# IO_EXPAND.net
KiCad netlist of a schematic drawn in Altium Designer
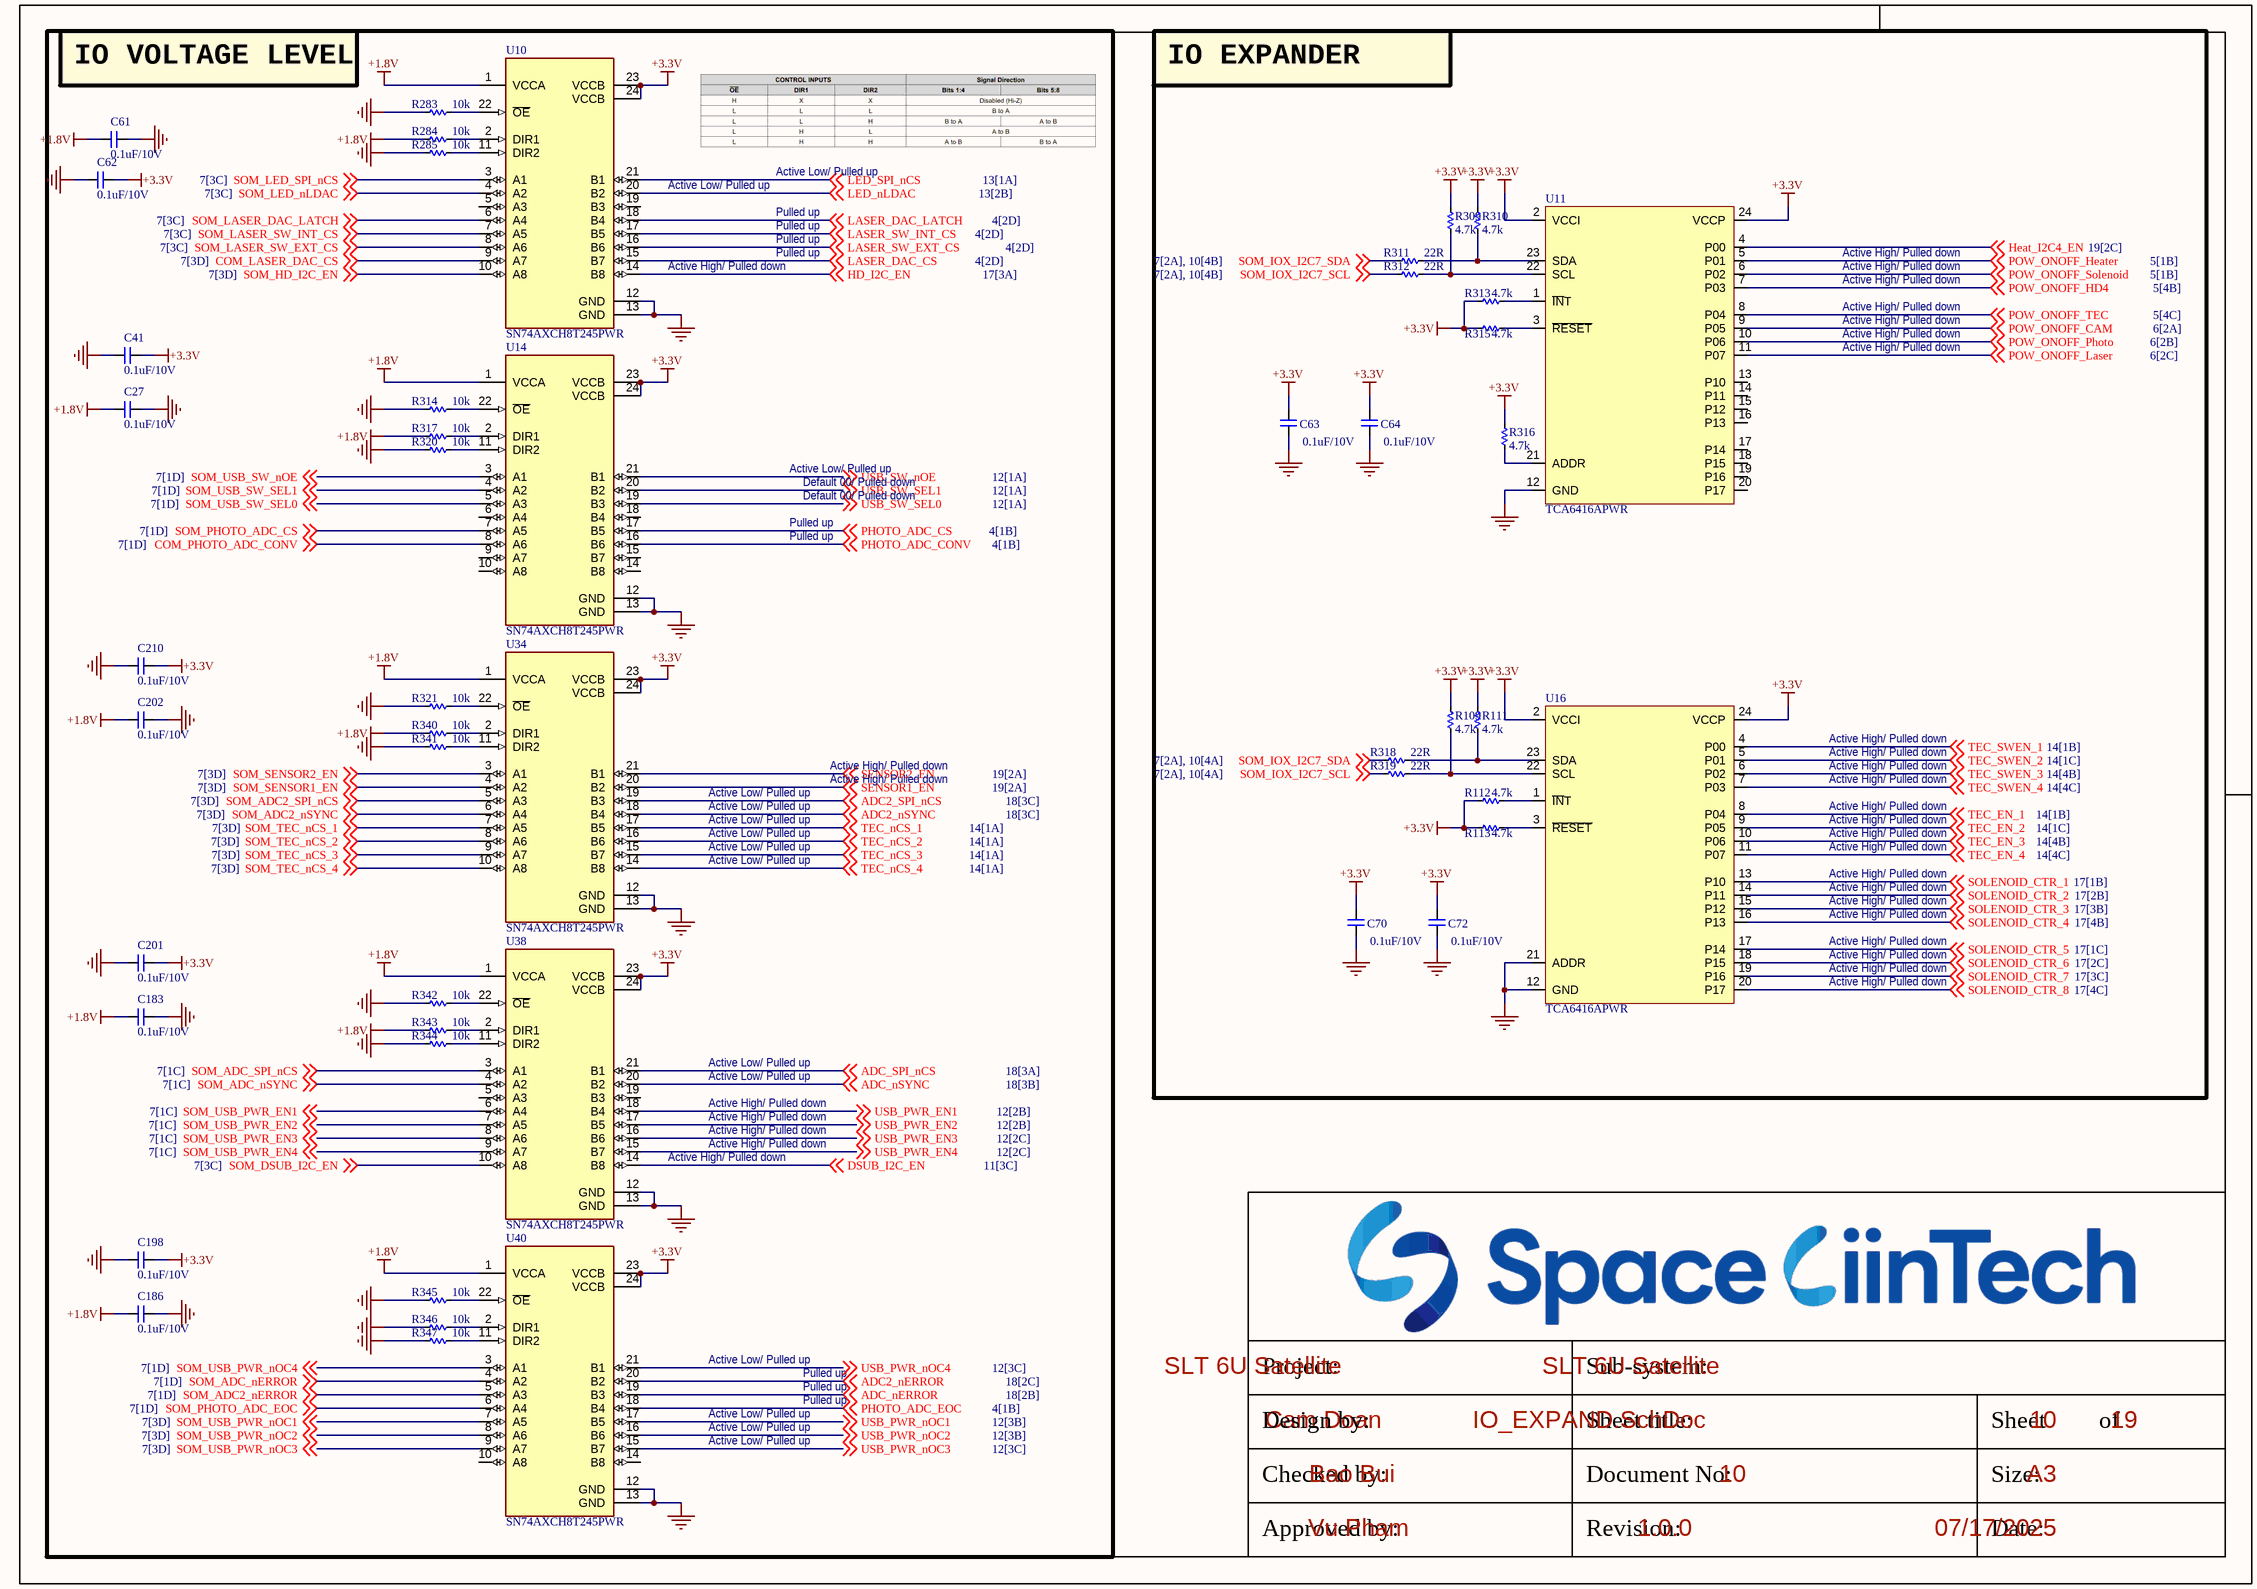
[diagram p0: IO_EXPAND.SchDoc]

(export (version "E")
  (design (tool "Eeschema 10.0.6"))
  (components
    (comp (ref "C27")
      (value "0.1uF/10V")
      (footprint "CAP_C_1005X60")
      (description "CAP CHIP")
      (libsource (lib "LABLIB") (part "_CAP_C_2"))
    )
    (comp (ref "C41")
      (value "0.1uF/10V")
      (footprint "CAP_C_1005X60")
      (description "CAP CHIP")
      (libsource (lib "LABLIB") (part "_CAP_C_2"))
    )
    (comp (ref "C61")
      (value "0.1uF/10V")
      (footprint "CAP_C_1005X60")
      (description "CAP CHIP")
      (libsource (lib "LABLIB") (part "_CAP_C_2"))
    )
    (comp (ref "C62")
      (value "0.1uF/10V")
      (footprint "CAP_C_1005X60")
      (description "CAP CHIP")
      (libsource (lib "LABLIB") (part "_CAP_C_2"))
    )
    (comp (ref "C63")
      (value "0.1uF/10V")
      (footprint "CAP_C_1005X60")
      (description "CAP CHIP")
      (libsource (lib "LABLIB") (part "_CAP_C_2"))
    )
    (comp (ref "C64")
      (value "0.1uF/10V")
      (footprint "CAP_C_1005X60")
      (description "CAP CHIP")
      (libsource (lib "LABLIB") (part "_CAP_C_2"))
    )
    (comp (ref "C70")
      (value "0.1uF/10V")
      (footprint "CAP_C_1005X60")
      (description "CAP CHIP")
      (libsource (lib "LABLIB") (part "_CAP_C_2"))
    )
    (comp (ref "C72")
      (value "0.1uF/10V")
      (footprint "CAP_C_1005X60")
      (description "CAP CHIP")
      (libsource (lib "LABLIB") (part "_CAP_C_2"))
    )
    (comp (ref "C183")
      (value "0.1uF/10V")
      (footprint "CAP_C_1005X60")
      (description "CAP CHIP")
      (libsource (lib "LABLIB") (part "_CAP_C_2"))
    )
    (comp (ref "C186")
      (value "0.1uF/10V")
      (footprint "CAP_C_1005X60")
      (description "CAP CHIP")
      (libsource (lib "LABLIB") (part "_CAP_C_2"))
    )
    (comp (ref "C198")
      (value "0.1uF/10V")
      (footprint "CAP_C_1005X60")
      (description "CAP CHIP")
      (libsource (lib "LABLIB") (part "_CAP_C_2"))
    )
    (comp (ref "C201")
      (value "0.1uF/10V")
      (footprint "CAP_C_1005X60")
      (description "CAP CHIP")
      (libsource (lib "LABLIB") (part "_CAP_C_2"))
    )
    (comp (ref "C202")
      (value "0.1uF/10V")
      (footprint "CAP_C_1005X60")
      (description "CAP CHIP")
      (libsource (lib "LABLIB") (part "_CAP_C_2"))
    )
    (comp (ref "C210")
      (value "0.1uF/10V")
      (footprint "CAP_C_1005X60")
      (description "CAP CHIP")
      (libsource (lib "LABLIB") (part "_CAP_C_2"))
    )
    (comp (ref "R109")
      (value "4.7k")
      (footprint "RES_C_1005X40")
      (description "RES")
      (libsource (lib "LABLIB") (part "_RES_B_2"))
    )
    (comp (ref "R111")
      (value "4.7k")
      (footprint "RES_C_1005X40")
      (description "RES")
      (libsource (lib "LABLIB") (part "_RES_B_2"))
    )
    (comp (ref "R112")
      (value "4.7k")
      (footprint "RES_C_1005X40")
      (description "RES")
      (libsource (lib "LABLIB") (part "_RES_B_2"))
    )
    (comp (ref "R113")
      (value "4.7k")
      (footprint "RES_C_1005X40")
      (description "RES")
      (libsource (lib "LABLIB") (part "_RES_B_2"))
    )
    (comp (ref "R283")
      (value "10k")
      (footprint "RES_C_1005X40")
      (description "RES")
      (libsource (lib "LABLIB") (part "_RES_B_2"))
    )
    (comp (ref "R284")
      (value "10k")
      (footprint "RES_C_1005X40")
      (description "RES")
      (libsource (lib "LABLIB") (part "_RES_B_2"))
    )
    (comp (ref "R285")
      (value "10k")
      (footprint "RES_C_1005X40")
      (description "RES")
      (libsource (lib "LABLIB") (part "_RES_B_2"))
    )
    (comp (ref "R309")
      (value "4.7k")
      (footprint "RES_C_1005X40")
      (description "RES")
      (libsource (lib "LABLIB") (part "_RES_B_2"))
    )
    (comp (ref "R310")
      (value "4.7k")
      (footprint "RES_C_1005X40")
      (description "RES")
      (libsource (lib "LABLIB") (part "_RES_B_2"))
    )
    (comp (ref "R311")
      (value "22R")
      (footprint "RES_C_1005X40")
      (description "RES")
      (libsource (lib "LABLIB") (part "_RES_B_2"))
    )
    (comp (ref "R312")
      (value "22R")
      (footprint "RES_C_1005X40")
      (description "RES")
      (libsource (lib "LABLIB") (part "_RES_B_2"))
    )
    (comp (ref "R313")
      (value "4.7k")
      (footprint "RES_C_1005X40")
      (description "RES")
      (libsource (lib "LABLIB") (part "_RES_B_2"))
    )
    (comp (ref "R314")
      (value "10k")
      (footprint "RES_C_1005X40")
      (description "RES")
      (libsource (lib "LABLIB") (part "_RES_B_2"))
    )
    (comp (ref "R315")
      (value "4.7k")
      (footprint "RES_C_1005X40")
      (description "RES")
      (libsource (lib "LABLIB") (part "_RES_B_2"))
    )
    (comp (ref "R316")
      (value "4.7k")
      (footprint "RES_C_1005X40")
      (description "RES")
      (libsource (lib "LABLIB") (part "_RES_B_2"))
    )
    (comp (ref "R317")
      (value "10k")
      (footprint "RES_C_1005X40")
      (description "RES")
      (libsource (lib "LABLIB") (part "_RES_B_2"))
    )
    (comp (ref "R318")
      (value "22R")
      (footprint "RES_C_1005X40")
      (description "RES")
      (libsource (lib "LABLIB") (part "_RES_B_2"))
    )
    (comp (ref "R319")
      (value "22R")
      (footprint "RES_C_1005X40")
      (description "RES")
      (libsource (lib "LABLIB") (part "_RES_B_2"))
    )
    (comp (ref "R320")
      (value "10k")
      (footprint "RES_C_1005X40")
      (description "RES")
      (libsource (lib "LABLIB") (part "_RES_B_2"))
    )
    (comp (ref "R321")
      (value "10k")
      (footprint "RES_C_1005X40")
      (description "RES")
      (libsource (lib "LABLIB") (part "_RES_B_2"))
    )
    (comp (ref "R340")
      (value "10k")
      (footprint "RES_C_1005X40")
      (description "RES")
      (libsource (lib "LABLIB") (part "_RES_B_2"))
    )
    (comp (ref "R341")
      (value "10k")
      (footprint "RES_C_1005X40")
      (description "RES")
      (libsource (lib "LABLIB") (part "_RES_B_2"))
    )
    (comp (ref "R342")
      (value "10k")
      (footprint "RES_C_1005X40")
      (description "RES")
      (libsource (lib "LABLIB") (part "_RES_B_2"))
    )
    (comp (ref "R343")
      (value "10k")
      (footprint "RES_C_1005X40")
      (description "RES")
      (libsource (lib "LABLIB") (part "_RES_B_2"))
    )
    (comp (ref "R344")
      (value "10k")
      (footprint "RES_C_1005X40")
      (description "RES")
      (libsource (lib "LABLIB") (part "_RES_B_2"))
    )
    (comp (ref "R345")
      (value "10k")
      (footprint "RES_C_1005X40")
      (description "RES")
      (libsource (lib "LABLIB") (part "_RES_B_2"))
    )
    (comp (ref "R346")
      (value "10k")
      (footprint "RES_C_1005X40")
      (description "RES")
      (libsource (lib "LABLIB") (part "_RES_B_2"))
    )
    (comp (ref "R347")
      (value "10k")
      (footprint "RES_C_1005X40")
      (description "RES")
      (libsource (lib "LABLIB") (part "_RES_B_2"))
    )
    (comp (ref "U10")
      (value "SN74AXCH8T245PWR")
      (footprint "SOP65P640X120-24N")
      (description "8-Bit Dual-Supply Bus Transceiver")
      (fields (field (name "MF") "Texas Instruments"))
      (libsource (lib "LABLIB") (part "IC_voltage_level_SN74AXCH8T245PWR"))
    )
    (comp (ref "U11")
      (value "TCA6416APWR")
      (footprint "SOP65P440W-24N")
      (libsource (lib "CAMERA_SchLib") (part "IC_I2Cto16IO_TCA6416APWR"))
    )
    (comp (ref "U14")
      (value "SN74AXCH8T245PWR")
      (footprint "SOP65P640X120-24N")
      (description "8-Bit Dual-Supply Bus Transceiver")
      (fields (field (name "MF") "Texas Instruments"))
      (libsource (lib "LABLIB") (part "IC_voltage_level_SN74AXCH8T245PWR"))
    )
    (comp (ref "U16")
      (value "TCA6416APWR")
      (footprint "SOP65P440W-24N")
      (libsource (lib "CAMERA_SchLib") (part "IC_I2Cto16IO_TCA6416APWR"))
    )
    (comp (ref "U34")
      (value "SN74AXCH8T245PWR")
      (footprint "SOP65P640X120-24N")
      (description "8-Bit Dual-Supply Bus Transceiver")
      (fields (field (name "MF") "Texas Instruments"))
      (libsource (lib "LABLIB") (part "IC_voltage_level_SN74AXCH8T245PWR"))
    )
    (comp (ref "U38")
      (value "SN74AXCH8T245PWR")
      (footprint "SOP65P640X120-24N")
      (description "8-Bit Dual-Supply Bus Transceiver")
      (fields (field (name "MF") "Texas Instruments"))
      (libsource (lib "LABLIB") (part "IC_voltage_level_SN74AXCH8T245PWR"))
    )
    (comp (ref "U40")
      (value "SN74AXCH8T245PWR")
      (footprint "SOP65P640X120-24N")
      (description "8-Bit Dual-Supply Bus Transceiver")
      (fields (field (name "MF") "Texas Instruments"))
      (libsource (lib "LABLIB") (part "IC_voltage_level_SN74AXCH8T245PWR"))
    )
  )
  (nets
    (net (code "1") (name "+1.8V") (class "Default")
      (node (ref "C183") (pin "2") (pinfunction "2_2") (pintype "passive"))
      (node (ref "C186") (pin "2") (pinfunction "2_2") (pintype "passive"))
      (node (ref "C202") (pin "2") (pinfunction "2_2") (pintype "passive"))
      (node (ref "C27") (pin "2") (pinfunction "2_2") (pintype "passive"))
      (node (ref "C61") (pin "2") (pinfunction "2_2") (pintype "passive"))
      (node (ref "R284") (pin "2") (pinfunction "2_2") (pintype "passive"))
      (node (ref "R317") (pin "2") (pinfunction "2_2") (pintype "passive"))
      (node (ref "R340") (pin "2") (pinfunction "2_2") (pintype "passive"))
      (node (ref "R343") (pin "2") (pinfunction "2_2") (pintype "passive"))
      (node (ref "U10") (pin "1") (pinfunction "VCCA_1") (pintype "power_in"))
      (node (ref "U14") (pin "1") (pinfunction "VCCA_1") (pintype "power_in"))
      (node (ref "U34") (pin "1") (pinfunction "VCCA_1") (pintype "power_in"))
      (node (ref "U38") (pin "1") (pinfunction "VCCA_1") (pintype "power_in"))
      (node (ref "U40") (pin "1") (pinfunction "VCCA_1") (pintype "power_in"))
    )
    (net (code "2") (name "+3.3V") (class "Default")
      (node (ref "C198") (pin "2") (pinfunction "2_2") (pintype "passive"))
      (node (ref "C201") (pin "2") (pinfunction "2_2") (pintype "passive"))
      (node (ref "C210") (pin "2") (pinfunction "2_2") (pintype "passive"))
      (node (ref "C41") (pin "2") (pinfunction "2_2") (pintype "passive"))
      (node (ref "C62") (pin "2") (pinfunction "2_2") (pintype "passive"))
      (node (ref "C63") (pin "2") (pinfunction "2_2") (pintype "passive"))
      (node (ref "C64") (pin "2") (pinfunction "2_2") (pintype "passive"))
      (node (ref "C70") (pin "2") (pinfunction "2_2") (pintype "passive"))
      (node (ref "C72") (pin "2") (pinfunction "2_2") (pintype "passive"))
      (node (ref "R109") (pin "1") (pinfunction "1_1") (pintype "passive"))
      (node (ref "R111") (pin "1") (pinfunction "1_1") (pintype "passive"))
      (node (ref "R112") (pin "1") (pinfunction "1_1") (pintype "passive"))
      (node (ref "R113") (pin "1") (pinfunction "1_1") (pintype "passive"))
      (node (ref "R309") (pin "1") (pinfunction "1_1") (pintype "passive"))
      (node (ref "R310") (pin "1") (pinfunction "1_1") (pintype "passive"))
      (node (ref "R313") (pin "1") (pinfunction "1_1") (pintype "passive"))
      (node (ref "R315") (pin "1") (pinfunction "1_1") (pintype "passive"))
      (node (ref "R316") (pin "2") (pinfunction "2_2") (pintype "passive"))
      (node (ref "U10") (pin "23") (pinfunction "VCCB_23") (pintype "power_in"))
      (node (ref "U10") (pin "24") (pinfunction "VCCB_24") (pintype "power_in"))
      (node (ref "U11") (pin "2") (pinfunction "VCCI_2") (pintype "passive"))
      (node (ref "U11") (pin "24") (pinfunction "VCCP_24") (pintype "passive"))
      (node (ref "U14") (pin "23") (pinfunction "VCCB_23") (pintype "power_in"))
      (node (ref "U14") (pin "24") (pinfunction "VCCB_24") (pintype "power_in"))
      (node (ref "U16") (pin "2") (pinfunction "VCCI_2") (pintype "passive"))
      (node (ref "U16") (pin "24") (pinfunction "VCCP_24") (pintype "passive"))
      (node (ref "U34") (pin "23") (pinfunction "VCCB_23") (pintype "power_in"))
      (node (ref "U34") (pin "24") (pinfunction "VCCB_24") (pintype "power_in"))
      (node (ref "U38") (pin "23") (pinfunction "VCCB_23") (pintype "power_in"))
      (node (ref "U38") (pin "24") (pinfunction "VCCB_24") (pintype "power_in"))
      (node (ref "U40") (pin "23") (pinfunction "VCCB_23") (pintype "power_in"))
      (node (ref "U40") (pin "24") (pinfunction "VCCB_24") (pintype "power_in"))
    )
    (net (code "3") (name "ADC2_SPI_nCS") (class "Default")
      (node (ref "U34") (pin "19") (pinfunction "B3_19") (pintype "bidirectional"))
    )
    (net (code "4") (name "ADC2_nERROR") (class "Default")
      (node (ref "U40") (pin "20") (pinfunction "B2_20") (pintype "bidirectional"))
    )
    (net (code "5") (name "ADC2_nSYNC") (class "Default")
      (node (ref "U34") (pin "18") (pinfunction "B4_18") (pintype "bidirectional"))
    )
    (net (code "6") (name "ADC_SPI_nCS") (class "Default")
      (node (ref "U38") (pin "21") (pinfunction "B1_21") (pintype "bidirectional"))
    )
    (net (code "7") (name "ADC_nERROR") (class "Default")
      (node (ref "U40") (pin "19") (pinfunction "B3_19") (pintype "bidirectional"))
    )
    (net (code "8") (name "ADC_nSYNC") (class "Default")
      (node (ref "U38") (pin "20") (pinfunction "B2_20") (pintype "bidirectional"))
    )
    (net (code "9") (name "COM_LASER_DAC_CS") (class "Default")
      (node (ref "U10") (pin "9") (pinfunction "A7_9") (pintype "bidirectional"))
    )
    (net (code "10") (name "COM_PHOTO_ADC_CONV") (class "Default")
      (node (ref "U14") (pin "8") (pinfunction "A6_8") (pintype "bidirectional"))
    )
    (net (code "11") (name "DSUB_I2C_EN") (class "Default")
      (node (ref "U38") (pin "14") (pinfunction "B8_14") (pintype "bidirectional"))
    )
    (net (code "12") (name "GND") (class "Default")
      (node (ref "C183") (pin "1") (pinfunction "1_1") (pintype "passive"))
      (node (ref "C186") (pin "1") (pinfunction "1_1") (pintype "passive"))
      (node (ref "C198") (pin "1") (pinfunction "1_1") (pintype "passive"))
      (node (ref "C201") (pin "1") (pinfunction "1_1") (pintype "passive"))
      (node (ref "C202") (pin "1") (pinfunction "1_1") (pintype "passive"))
      (node (ref "C210") (pin "1") (pinfunction "1_1") (pintype "passive"))
      (node (ref "C27") (pin "1") (pinfunction "1_1") (pintype "passive"))
      (node (ref "C41") (pin "1") (pinfunction "1_1") (pintype "passive"))
      (node (ref "C61") (pin "1") (pinfunction "1_1") (pintype "passive"))
      (node (ref "C62") (pin "1") (pinfunction "1_1") (pintype "passive"))
      (node (ref "C63") (pin "1") (pinfunction "1_1") (pintype "passive"))
      (node (ref "C64") (pin "1") (pinfunction "1_1") (pintype "passive"))
      (node (ref "C70") (pin "1") (pinfunction "1_1") (pintype "passive"))
      (node (ref "C72") (pin "1") (pinfunction "1_1") (pintype "passive"))
      (node (ref "R283") (pin "2") (pinfunction "2_2") (pintype "passive"))
      (node (ref "R285") (pin "2") (pinfunction "2_2") (pintype "passive"))
      (node (ref "R314") (pin "2") (pinfunction "2_2") (pintype "passive"))
      (node (ref "R320") (pin "2") (pinfunction "2_2") (pintype "passive"))
      (node (ref "R321") (pin "2") (pinfunction "2_2") (pintype "passive"))
      (node (ref "R341") (pin "2") (pinfunction "2_2") (pintype "passive"))
      (node (ref "R342") (pin "2") (pinfunction "2_2") (pintype "passive"))
      (node (ref "R344") (pin "2") (pinfunction "2_2") (pintype "passive"))
      (node (ref "R345") (pin "2") (pinfunction "2_2") (pintype "passive"))
      (node (ref "R346") (pin "2") (pinfunction "2_2") (pintype "passive"))
      (node (ref "R347") (pin "2") (pinfunction "2_2") (pintype "passive"))
      (node (ref "U10") (pin "12") (pinfunction "GND_12") (pintype "power_in"))
      (node (ref "U10") (pin "13") (pinfunction "GND_13") (pintype "power_in"))
      (node (ref "U11") (pin "12") (pinfunction "GND_12") (pintype "passive"))
      (node (ref "U14") (pin "12") (pinfunction "GND_12") (pintype "power_in"))
      (node (ref "U14") (pin "13") (pinfunction "GND_13") (pintype "power_in"))
      (node (ref "U16") (pin "12") (pinfunction "GND_12") (pintype "passive"))
      (node (ref "U16") (pin "21") (pinfunction "ADDR_21") (pintype "passive"))
      (node (ref "U34") (pin "12") (pinfunction "GND_12") (pintype "power_in"))
      (node (ref "U34") (pin "13") (pinfunction "GND_13") (pintype "power_in"))
      (node (ref "U38") (pin "12") (pinfunction "GND_12") (pintype "power_in"))
      (node (ref "U38") (pin "13") (pinfunction "GND_13") (pintype "power_in"))
      (node (ref "U40") (pin "12") (pinfunction "GND_12") (pintype "power_in"))
      (node (ref "U40") (pin "13") (pinfunction "GND_13") (pintype "power_in"))
    )
    (net (code "13") (name "HD_I2C_EN") (class "Default")
      (node (ref "U10") (pin "14") (pinfunction "B8_14") (pintype "bidirectional"))
    )
    (net (code "14") (name "Heat_I2C4_EN") (class "Default")
      (node (ref "U11") (pin "4") (pinfunction "P00_4") (pintype "passive"))
    )
    (net (code "15") (name "LASER_DAC_CS") (class "Default")
      (node (ref "U10") (pin "15") (pinfunction "B7_15") (pintype "bidirectional"))
    )
    (net (code "16") (name "LASER_DAC_LATCH") (class "Default")
      (node (ref "U10") (pin "18") (pinfunction "B4_18") (pintype "bidirectional"))
    )
    (net (code "17") (name "LASER_SW_EXT_CS") (class "Default")
      (node (ref "U10") (pin "16") (pinfunction "B6_16") (pintype "bidirectional"))
    )
    (net (code "18") (name "LASER_SW_INT_CS") (class "Default")
      (node (ref "U10") (pin "17") (pinfunction "B5_17") (pintype "bidirectional"))
    )
    (net (code "19") (name "LED_SPI_nCS") (class "Default")
      (node (ref "U10") (pin "21") (pinfunction "B1_21") (pintype "bidirectional"))
    )
    (net (code "20") (name "LED_nLDAC") (class "Default")
      (node (ref "U10") (pin "20") (pinfunction "B2_20") (pintype "bidirectional"))
    )
    (net (code "21") (name "Net-(U10-DIR1)") (class "Default")
      (node (ref "R284") (pin "1") (pinfunction "1_1") (pintype "passive"))
      (node (ref "U10") (pin "2") (pinfunction "DIR1_2") (pintype "input"))
    )
    (net (code "22") (name "Net-(U10-DIR2)") (class "Default")
      (node (ref "R285") (pin "1") (pinfunction "1_1") (pintype "passive"))
      (node (ref "U10") (pin "11") (pinfunction "DIR2_11") (pintype "input"))
    )
    (net (code "23") (name "Net-(U10-~{OE})") (class "Default")
      (node (ref "R283") (pin "1") (pinfunction "1_1") (pintype "passive"))
      (node (ref "U10") (pin "22") (pinfunction "~{OE}_22") (pintype "input"))
    )
    (net (code "24") (name "Net-(U11-ADDR)") (class "Default")
      (node (ref "R316") (pin "1") (pinfunction "1_1") (pintype "passive"))
      (node (ref "U11") (pin "21") (pinfunction "ADDR_21") (pintype "passive"))
    )
    (net (code "25") (name "Net-(U11-SCL)") (class "Default")
      (node (ref "R309") (pin "2") (pinfunction "2_2") (pintype "passive"))
      (node (ref "R312") (pin "2") (pinfunction "2_2") (pintype "passive"))
      (node (ref "U11") (pin "22") (pinfunction "SCL_22") (pintype "passive"))
    )
    (net (code "26") (name "Net-(U11-SDA)") (class "Default")
      (node (ref "R310") (pin "2") (pinfunction "2_2") (pintype "passive"))
      (node (ref "R311") (pin "2") (pinfunction "2_2") (pintype "passive"))
      (node (ref "U11") (pin "23") (pinfunction "SDA_23") (pintype "passive"))
    )
    (net (code "27") (name "Net-(U11-~{IN}T)") (class "Default")
      (node (ref "R313") (pin "2") (pinfunction "2_2") (pintype "passive"))
      (node (ref "U11") (pin "1") (pinfunction "~{IN}T_1") (pintype "passive"))
    )
    (net (code "28") (name "Net-(U11-~{RESET})") (class "Default")
      (node (ref "R315") (pin "2") (pinfunction "2_2") (pintype "passive"))
      (node (ref "U11") (pin "3") (pinfunction "~{RESET}_3") (pintype "passive"))
    )
    (net (code "29") (name "Net-(U14-DIR1)") (class "Default")
      (node (ref "R317") (pin "1") (pinfunction "1_1") (pintype "passive"))
      (node (ref "U14") (pin "2") (pinfunction "DIR1_2") (pintype "input"))
    )
    (net (code "30") (name "Net-(U14-DIR2)") (class "Default")
      (node (ref "R320") (pin "1") (pinfunction "1_1") (pintype "passive"))
      (node (ref "U14") (pin "11") (pinfunction "DIR2_11") (pintype "input"))
    )
    (net (code "31") (name "Net-(U14-~{OE})") (class "Default")
      (node (ref "R314") (pin "1") (pinfunction "1_1") (pintype "passive"))
      (node (ref "U14") (pin "22") (pinfunction "~{OE}_22") (pintype "input"))
    )
    (net (code "32") (name "Net-(U16-SCL)") (class "Default")
      (node (ref "R109") (pin "2") (pinfunction "2_2") (pintype "passive"))
      (node (ref "R319") (pin "2") (pinfunction "2_2") (pintype "passive"))
      (node (ref "U16") (pin "22") (pinfunction "SCL_22") (pintype "passive"))
    )
    (net (code "33") (name "Net-(U16-SDA)") (class "Default")
      (node (ref "R111") (pin "2") (pinfunction "2_2") (pintype "passive"))
      (node (ref "R318") (pin "2") (pinfunction "2_2") (pintype "passive"))
      (node (ref "U16") (pin "23") (pinfunction "SDA_23") (pintype "passive"))
    )
    (net (code "34") (name "Net-(U16-~{IN}T)") (class "Default")
      (node (ref "R112") (pin "2") (pinfunction "2_2") (pintype "passive"))
      (node (ref "U16") (pin "1") (pinfunction "~{IN}T_1") (pintype "passive"))
    )
    (net (code "35") (name "Net-(U16-~{RESET})") (class "Default")
      (node (ref "R113") (pin "2") (pinfunction "2_2") (pintype "passive"))
      (node (ref "U16") (pin "3") (pinfunction "~{RESET}_3") (pintype "passive"))
    )
    (net (code "36") (name "Net-(U34-DIR1)") (class "Default")
      (node (ref "R340") (pin "1") (pinfunction "1_1") (pintype "passive"))
      (node (ref "U34") (pin "2") (pinfunction "DIR1_2") (pintype "input"))
    )
    (net (code "37") (name "Net-(U34-DIR2)") (class "Default")
      (node (ref "R341") (pin "1") (pinfunction "1_1") (pintype "passive"))
      (node (ref "U34") (pin "11") (pinfunction "DIR2_11") (pintype "input"))
    )
    (net (code "38") (name "Net-(U34-~{OE})") (class "Default")
      (node (ref "R321") (pin "1") (pinfunction "1_1") (pintype "passive"))
      (node (ref "U34") (pin "22") (pinfunction "~{OE}_22") (pintype "input"))
    )
    (net (code "39") (name "Net-(U38-DIR1)") (class "Default")
      (node (ref "R343") (pin "1") (pinfunction "1_1") (pintype "passive"))
      (node (ref "U38") (pin "2") (pinfunction "DIR1_2") (pintype "input"))
    )
    (net (code "40") (name "Net-(U38-DIR2)") (class "Default")
      (node (ref "R344") (pin "1") (pinfunction "1_1") (pintype "passive"))
      (node (ref "U38") (pin "11") (pinfunction "DIR2_11") (pintype "input"))
    )
    (net (code "41") (name "Net-(U38-~{OE})") (class "Default")
      (node (ref "R342") (pin "1") (pinfunction "1_1") (pintype "passive"))
      (node (ref "U38") (pin "22") (pinfunction "~{OE}_22") (pintype "input"))
    )
    (net (code "42") (name "Net-(U40-DIR1)") (class "Default")
      (node (ref "R346") (pin "1") (pinfunction "1_1") (pintype "passive"))
      (node (ref "U40") (pin "2") (pinfunction "DIR1_2") (pintype "input"))
    )
    (net (code "43") (name "Net-(U40-DIR2)") (class "Default")
      (node (ref "R347") (pin "1") (pinfunction "1_1") (pintype "passive"))
      (node (ref "U40") (pin "11") (pinfunction "DIR2_11") (pintype "input"))
    )
    (net (code "44") (name "Net-(U40-~{OE})") (class "Default")
      (node (ref "R345") (pin "1") (pinfunction "1_1") (pintype "passive"))
      (node (ref "U40") (pin "22") (pinfunction "~{OE}_22") (pintype "input"))
    )
    (net (code "45") (name "PHOTO_ADC_CONV") (class "Default")
      (node (ref "U14") (pin "16") (pinfunction "B6_16") (pintype "bidirectional"))
    )
    (net (code "46") (name "PHOTO_ADC_CS") (class "Default")
      (node (ref "U14") (pin "17") (pinfunction "B5_17") (pintype "bidirectional"))
    )
    (net (code "47") (name "PHOTO_ADC_EOC") (class "Default")
      (node (ref "U40") (pin "18") (pinfunction "B4_18") (pintype "bidirectional"))
    )
    (net (code "48") (name "POW_ONOFF_CAM") (class "Default")
      (node (ref "U11") (pin "9") (pinfunction "P05_9") (pintype "passive"))
    )
    (net (code "49") (name "POW_ONOFF_HD4") (class "Default")
      (node (ref "U11") (pin "7") (pinfunction "P03_7") (pintype "passive"))
    )
    (net (code "50") (name "POW_ONOFF_Heater") (class "Default")
      (node (ref "U11") (pin "5") (pinfunction "P01_5") (pintype "passive"))
    )
    (net (code "51") (name "POW_ONOFF_Laser") (class "Default")
      (node (ref "U11") (pin "11") (pinfunction "P07_11") (pintype "passive"))
    )
    (net (code "52") (name "POW_ONOFF_Photo") (class "Default")
      (node (ref "U11") (pin "10") (pinfunction "P06_10") (pintype "passive"))
    )
    (net (code "53") (name "POW_ONOFF_Solenoid") (class "Default")
      (node (ref "U11") (pin "6") (pinfunction "P02_6") (pintype "passive"))
    )
    (net (code "54") (name "POW_ONOFF_TEC") (class "Default")
      (node (ref "U11") (pin "8") (pinfunction "P04_8") (pintype "passive"))
    )
    (net (code "55") (name "SENSOR1_EN") (class "Default")
      (node (ref "U34") (pin "20") (pinfunction "B2_20") (pintype "bidirectional"))
    )
    (net (code "56") (name "SENSOR2_EN") (class "Default")
      (node (ref "U34") (pin "21") (pinfunction "B1_21") (pintype "bidirectional"))
    )
    (net (code "57") (name "SOLENOID_CTR_1") (class "Default")
      (node (ref "U16") (pin "13") (pinfunction "P10_13") (pintype "passive"))
    )
    (net (code "58") (name "SOLENOID_CTR_2") (class "Default")
      (node (ref "U16") (pin "14") (pinfunction "P11_14") (pintype "passive"))
    )
    (net (code "59") (name "SOLENOID_CTR_3") (class "Default")
      (node (ref "U16") (pin "15") (pinfunction "P12_15") (pintype "passive"))
    )
    (net (code "60") (name "SOLENOID_CTR_4") (class "Default")
      (node (ref "U16") (pin "16") (pinfunction "P13_16") (pintype "passive"))
    )
    (net (code "61") (name "SOLENOID_CTR_5") (class "Default")
      (node (ref "U16") (pin "17") (pinfunction "P14_17") (pintype "passive"))
    )
    (net (code "62") (name "SOLENOID_CTR_6") (class "Default")
      (node (ref "U16") (pin "18") (pinfunction "P15_18") (pintype "passive"))
    )
    (net (code "63") (name "SOLENOID_CTR_7") (class "Default")
      (node (ref "U16") (pin "19") (pinfunction "P16_19") (pintype "passive"))
    )
    (net (code "64") (name "SOLENOID_CTR_8") (class "Default")
      (node (ref "U16") (pin "20") (pinfunction "P17_20") (pintype "passive"))
    )
    (net (code "65") (name "SOM_ADC2_SPI_nCS") (class "Default")
      (node (ref "U34") (pin "5") (pinfunction "A3_5") (pintype "bidirectional"))
    )
    (net (code "66") (name "SOM_ADC2_nERROR") (class "Default")
      (node (ref "U40") (pin "5") (pinfunction "A3_5") (pintype "bidirectional"))
    )
    (net (code "67") (name "SOM_ADC2_nSYNC") (class "Default")
      (node (ref "U34") (pin "6") (pinfunction "A4_6") (pintype "bidirectional"))
    )
    (net (code "68") (name "SOM_ADC_SPI_nCS") (class "Default")
      (node (ref "U38") (pin "3") (pinfunction "A1_3") (pintype "bidirectional"))
    )
    (net (code "69") (name "SOM_ADC_nERROR") (class "Default")
      (node (ref "U40") (pin "4") (pinfunction "A2_4") (pintype "bidirectional"))
    )
    (net (code "70") (name "SOM_ADC_nSYNC") (class "Default")
      (node (ref "U38") (pin "4") (pinfunction "A2_4") (pintype "bidirectional"))
    )
    (net (code "71") (name "SOM_DSUB_I2C_EN") (class "Default")
      (node (ref "U38") (pin "10") (pinfunction "A8_10") (pintype "bidirectional"))
    )
    (net (code "72") (name "SOM_HD_I2C_EN") (class "Default")
      (node (ref "U10") (pin "10") (pinfunction "A8_10") (pintype "bidirectional"))
    )
    (net (code "73") (name "SOM_IOX_I2C7_SCL") (class "Default")
      (node (ref "R312") (pin "1") (pinfunction "1_1") (pintype "passive"))
      (node (ref "R319") (pin "1") (pinfunction "1_1") (pintype "passive"))
    )
    (net (code "74") (name "SOM_IOX_I2C7_SDA") (class "Default")
      (node (ref "R311") (pin "1") (pinfunction "1_1") (pintype "passive"))
      (node (ref "R318") (pin "1") (pinfunction "1_1") (pintype "passive"))
    )
    (net (code "75") (name "SOM_LASER_DAC_LATCH") (class "Default")
      (node (ref "U10") (pin "6") (pinfunction "A4_6") (pintype "bidirectional"))
    )
    (net (code "76") (name "SOM_LASER_SW_EXT_CS") (class "Default")
      (node (ref "U10") (pin "8") (pinfunction "A6_8") (pintype "bidirectional"))
    )
    (net (code "77") (name "SOM_LASER_SW_INT_CS") (class "Default")
      (node (ref "U10") (pin "7") (pinfunction "A5_7") (pintype "bidirectional"))
    )
    (net (code "78") (name "SOM_LED_SPI_nCS") (class "Default")
      (node (ref "U10") (pin "3") (pinfunction "A1_3") (pintype "bidirectional"))
    )
    (net (code "79") (name "SOM_LED_nLDAC") (class "Default")
      (node (ref "U10") (pin "4") (pinfunction "A2_4") (pintype "bidirectional"))
    )
    (net (code "80") (name "SOM_PHOTO_ADC_CS") (class "Default")
      (node (ref "U14") (pin "7") (pinfunction "A5_7") (pintype "bidirectional"))
    )
    (net (code "81") (name "SOM_PHOTO_ADC_EOC") (class "Default")
      (node (ref "U40") (pin "6") (pinfunction "A4_6") (pintype "bidirectional"))
    )
    (net (code "82") (name "SOM_SENSOR1_EN") (class "Default")
      (node (ref "U34") (pin "4") (pinfunction "A2_4") (pintype "bidirectional"))
    )
    (net (code "83") (name "SOM_SENSOR2_EN") (class "Default")
      (node (ref "U34") (pin "3") (pinfunction "A1_3") (pintype "bidirectional"))
    )
    (net (code "84") (name "SOM_TEC_nCS_1") (class "Default")
      (node (ref "U34") (pin "7") (pinfunction "A5_7") (pintype "bidirectional"))
    )
    (net (code "85") (name "SOM_TEC_nCS_2") (class "Default")
      (node (ref "U34") (pin "8") (pinfunction "A6_8") (pintype "bidirectional"))
    )
    (net (code "86") (name "SOM_TEC_nCS_3") (class "Default")
      (node (ref "U34") (pin "9") (pinfunction "A7_9") (pintype "bidirectional"))
    )
    (net (code "87") (name "SOM_TEC_nCS_4") (class "Default")
      (node (ref "U34") (pin "10") (pinfunction "A8_10") (pintype "bidirectional"))
    )
    (net (code "88") (name "SOM_USB_PWR_EN1") (class "Default")
      (node (ref "U38") (pin "6") (pinfunction "A4_6") (pintype "bidirectional"))
    )
    (net (code "89") (name "SOM_USB_PWR_EN2") (class "Default")
      (node (ref "U38") (pin "7") (pinfunction "A5_7") (pintype "bidirectional"))
    )
    (net (code "90") (name "SOM_USB_PWR_EN3") (class "Default")
      (node (ref "U38") (pin "8") (pinfunction "A6_8") (pintype "bidirectional"))
    )
    (net (code "91") (name "SOM_USB_PWR_EN4") (class "Default")
      (node (ref "U38") (pin "9") (pinfunction "A7_9") (pintype "bidirectional"))
    )
    (net (code "92") (name "SOM_USB_PWR_nOC1") (class "Default")
      (node (ref "U40") (pin "7") (pinfunction "A5_7") (pintype "bidirectional"))
    )
    (net (code "93") (name "SOM_USB_PWR_nOC2") (class "Default")
      (node (ref "U40") (pin "8") (pinfunction "A6_8") (pintype "bidirectional"))
    )
    (net (code "94") (name "SOM_USB_PWR_nOC3") (class "Default")
      (node (ref "U40") (pin "9") (pinfunction "A7_9") (pintype "bidirectional"))
    )
    (net (code "95") (name "SOM_USB_PWR_nOC4") (class "Default")
      (node (ref "U40") (pin "3") (pinfunction "A1_3") (pintype "bidirectional"))
    )
    (net (code "96") (name "SOM_USB_SW_SEL0") (class "Default")
      (node (ref "U14") (pin "5") (pinfunction "A3_5") (pintype "bidirectional"))
    )
    (net (code "97") (name "SOM_USB_SW_SEL1") (class "Default")
      (node (ref "U14") (pin "4") (pinfunction "A2_4") (pintype "bidirectional"))
    )
    (net (code "98") (name "SOM_USB_SW_nOE") (class "Default")
      (node (ref "U14") (pin "3") (pinfunction "A1_3") (pintype "bidirectional"))
    )
    (net (code "99") (name "TEC_EN_1") (class "Default")
      (node (ref "U16") (pin "8") (pinfunction "P04_8") (pintype "passive"))
    )
    (net (code "100") (name "TEC_EN_2") (class "Default")
      (node (ref "U16") (pin "9") (pinfunction "P05_9") (pintype "passive"))
    )
    (net (code "101") (name "TEC_EN_3") (class "Default")
      (node (ref "U16") (pin "10") (pinfunction "P06_10") (pintype "passive"))
    )
    (net (code "102") (name "TEC_EN_4") (class "Default")
      (node (ref "U16") (pin "11") (pinfunction "P07_11") (pintype "passive"))
    )
    (net (code "103") (name "TEC_SWEN_1") (class "Default")
      (node (ref "U16") (pin "4") (pinfunction "P00_4") (pintype "passive"))
    )
    (net (code "104") (name "TEC_SWEN_2") (class "Default")
      (node (ref "U16") (pin "5") (pinfunction "P01_5") (pintype "passive"))
    )
    (net (code "105") (name "TEC_SWEN_3") (class "Default")
      (node (ref "U16") (pin "6") (pinfunction "P02_6") (pintype "passive"))
    )
    (net (code "106") (name "TEC_SWEN_4") (class "Default")
      (node (ref "U16") (pin "7") (pinfunction "P03_7") (pintype "passive"))
    )
    (net (code "107") (name "TEC_nCS_1") (class "Default")
      (node (ref "U34") (pin "17") (pinfunction "B5_17") (pintype "bidirectional"))
    )
    (net (code "108") (name "TEC_nCS_2") (class "Default")
      (node (ref "U34") (pin "16") (pinfunction "B6_16") (pintype "bidirectional"))
    )
    (net (code "109") (name "TEC_nCS_3") (class "Default")
      (node (ref "U34") (pin "15") (pinfunction "B7_15") (pintype "bidirectional"))
    )
    (net (code "110") (name "TEC_nCS_4") (class "Default")
      (node (ref "U34") (pin "14") (pinfunction "B8_14") (pintype "bidirectional"))
    )
    (net (code "111") (name "USB_PWR_EN1") (class "Default")
      (node (ref "U38") (pin "18") (pinfunction "B4_18") (pintype "bidirectional"))
    )
    (net (code "112") (name "USB_PWR_EN2") (class "Default")
      (node (ref "U38") (pin "17") (pinfunction "B5_17") (pintype "bidirectional"))
    )
    (net (code "113") (name "USB_PWR_EN3") (class "Default")
      (node (ref "U38") (pin "16") (pinfunction "B6_16") (pintype "bidirectional"))
    )
    (net (code "114") (name "USB_PWR_EN4") (class "Default")
      (node (ref "U38") (pin "15") (pinfunction "B7_15") (pintype "bidirectional"))
    )
    (net (code "115") (name "USB_PWR_nOC1") (class "Default")
      (node (ref "U40") (pin "17") (pinfunction "B5_17") (pintype "bidirectional"))
    )
    (net (code "116") (name "USB_PWR_nOC2") (class "Default")
      (node (ref "U40") (pin "16") (pinfunction "B6_16") (pintype "bidirectional"))
    )
    (net (code "117") (name "USB_PWR_nOC3") (class "Default")
      (node (ref "U40") (pin "15") (pinfunction "B7_15") (pintype "bidirectional"))
    )
    (net (code "118") (name "USB_PWR_nOC4") (class "Default")
      (node (ref "U40") (pin "21") (pinfunction "B1_21") (pintype "bidirectional"))
    )
    (net (code "119") (name "USB_SW_SEL0") (class "Default")
      (node (ref "U14") (pin "19") (pinfunction "B3_19") (pintype "bidirectional"))
    )
    (net (code "120") (name "USB_SW_SEL1") (class "Default")
      (node (ref "U14") (pin "20") (pinfunction "B2_20") (pintype "bidirectional"))
    )
    (net (code "121") (name "USB_SW_nOE") (class "Default")
      (node (ref "U14") (pin "21") (pinfunction "B1_21") (pintype "bidirectional"))
    )
    (net (code "122") (name "unconnected-(U10-A3-Pad5)") (class "Default")
      (node (ref "U10") (pin "5") (pinfunction "A3_5") (pintype "bidirectional"))
    )
    (net (code "123") (name "unconnected-(U10-B3-Pad19)") (class "Default")
      (node (ref "U10") (pin "19") (pinfunction "B3_19") (pintype "bidirectional"))
    )
    (net (code "124") (name "unconnected-(U11-P10-Pad13)") (class "Default")
      (node (ref "U11") (pin "13") (pinfunction "P10_13") (pintype "passive"))
    )
    (net (code "125") (name "unconnected-(U11-P11-Pad14)") (class "Default")
      (node (ref "U11") (pin "14") (pinfunction "P11_14") (pintype "passive"))
    )
    (net (code "126") (name "unconnected-(U11-P12-Pad15)") (class "Default")
      (node (ref "U11") (pin "15") (pinfunction "P12_15") (pintype "passive"))
    )
    (net (code "127") (name "unconnected-(U11-P13-Pad16)") (class "Default")
      (node (ref "U11") (pin "16") (pinfunction "P13_16") (pintype "passive"))
    )
    (net (code "128") (name "unconnected-(U11-P14-Pad17)") (class "Default")
      (node (ref "U11") (pin "17") (pinfunction "P14_17") (pintype "passive"))
    )
    (net (code "129") (name "unconnected-(U11-P15-Pad18)") (class "Default")
      (node (ref "U11") (pin "18") (pinfunction "P15_18") (pintype "passive"))
    )
    (net (code "130") (name "unconnected-(U11-P16-Pad19)") (class "Default")
      (node (ref "U11") (pin "19") (pinfunction "P16_19") (pintype "passive"))
    )
    (net (code "131") (name "unconnected-(U11-P17-Pad20)") (class "Default")
      (node (ref "U11") (pin "20") (pinfunction "P17_20") (pintype "passive"))
    )
    (net (code "132") (name "unconnected-(U14-A4-Pad6)") (class "Default")
      (node (ref "U14") (pin "6") (pinfunction "A4_6") (pintype "bidirectional"))
    )
    (net (code "133") (name "unconnected-(U14-A7-Pad9)") (class "Default")
      (node (ref "U14") (pin "9") (pinfunction "A7_9") (pintype "bidirectional"))
    )
    (net (code "134") (name "unconnected-(U14-A8-Pad10)") (class "Default")
      (node (ref "U14") (pin "10") (pinfunction "A8_10") (pintype "bidirectional"))
    )
    (net (code "135") (name "unconnected-(U14-B4-Pad18)") (class "Default")
      (node (ref "U14") (pin "18") (pinfunction "B4_18") (pintype "bidirectional"))
    )
    (net (code "136") (name "unconnected-(U14-B7-Pad15)") (class "Default")
      (node (ref "U14") (pin "15") (pinfunction "B7_15") (pintype "bidirectional"))
    )
    (net (code "137") (name "unconnected-(U14-B8-Pad14)") (class "Default")
      (node (ref "U14") (pin "14") (pinfunction "B8_14") (pintype "bidirectional"))
    )
    (net (code "138") (name "unconnected-(U38-A3-Pad5)") (class "Default")
      (node (ref "U38") (pin "5") (pinfunction "A3_5") (pintype "bidirectional"))
    )
    (net (code "139") (name "unconnected-(U38-B3-Pad19)") (class "Default")
      (node (ref "U38") (pin "19") (pinfunction "B3_19") (pintype "bidirectional"))
    )
    (net (code "140") (name "unconnected-(U40-A8-Pad10)") (class "Default")
      (node (ref "U40") (pin "10") (pinfunction "A8_10") (pintype "bidirectional"))
    )
    (net (code "141") (name "unconnected-(U40-B8-Pad14)") (class "Default")
      (node (ref "U40") (pin "14") (pinfunction "B8_14") (pintype "bidirectional"))
    )
  )
)
